# 2_IIP_RBF.net
KiCad netlist of a schematic drawn in Altium Designer
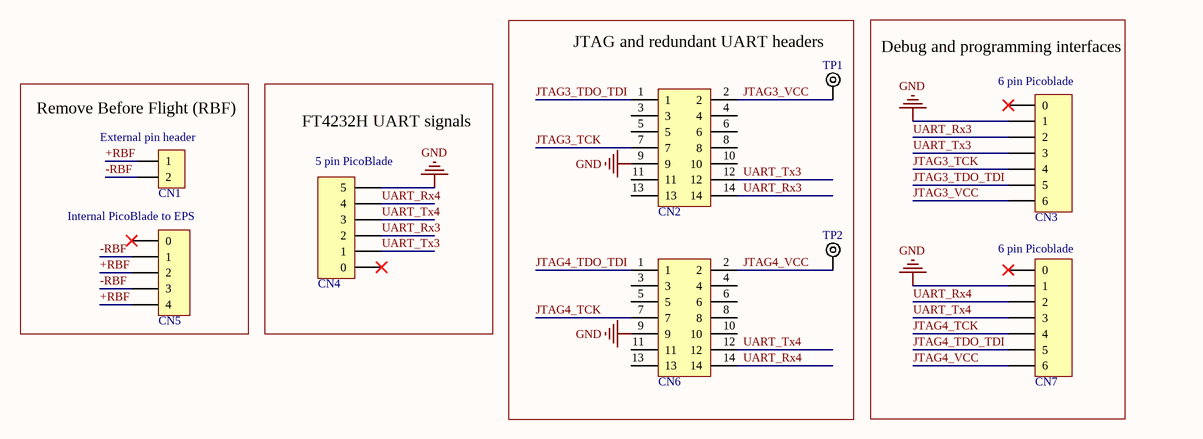
[diagram p0: 2_IIP_RBF.SchDoc]

(export (version "E")
  (design (tool "Eeschema 10.0.6"))
  (components
    (comp (ref "CN1")
      (value "2 POS Pin Header")
      (footprint "CONN HEADER VERT 2POS 2.54mm")
      (description "M20 HDR, PIN, SIL, VERT, 2W")
      (fields (field (name "MANUFACTURER") "Harwin") (field (name "VOLTAGE") "50V"))
      (libsource (lib "IB_floripasat2") (part "M20-9990245"))
    )
    (comp (ref "CN2")
      (value "7 POS dual line Pin Header 2.54mm")
      (footprint "CONN HEADER VERT 14POS 2.54MM")
      (description "Headers & Wire Housings 07+07 DIL VERTICAL PIN HEADER GOLD HT")
      (fields (field (name "MANUFACTURER") "Harwin") (field (name "MANUFACTURER PART NUMBER") "M20-9980745"))
      (libsource (lib "IB_floripasat2") (part "M20-9980745"))
    )
    (comp (ref "CN3")
      (value "6 pin Picoblade")
      (footprint "PICO BLADE 0533980671")
      (description "1.25mm Pitch PicoBlade™ Header, Surface Mount, Vertical, 6 Circuits")
      (fields (field (name "MANUFACTURER") "Molex") (field (name "MANUFACTURER PART NUMBER") "53398-0671"))
      (libsource (lib "IB_floripasat2") (part "53398-0671"))
    )
    (comp (ref "CN4")
      (value "5 pin PicoBlade")
      (footprint "PICO BLADE 0533980571")
      (description "Wire-To-Board Connector, Vertical, PicoBlade 53398 Series, Surface Mount, Header, 5, 1.25 mm")
      (fields (field (name "MANUFACTURER") "Molex") (field (name "MANUFACTURER PART NUMBER") "53398-0571"))
      (libsource (lib "IB_floripasat2") (part "53398-0571"))
    )
    (comp (ref "CN5")
      (value "4 pin Picoblade")
      (footprint "PICO BLADE 0533980471")
      (description "Connector Header Surface Mount 4 position 0.049\" (1.25mm)")
      (fields (field (name "MANUFACTURER") "Molex") (field (name "MANUFACTURER PART NUMBER") "53398-0471"))
      (libsource (lib "IB_floripasat2") (part "0533980471"))
    )
    (comp (ref "CN6")
      (value "7 POS dual line Pin Header 2.54mm")
      (footprint "CONN HEADER VERT 14POS 2.54MM")
      (description "Headers & Wire Housings 07+07 DIL VERTICAL PIN HEADER GOLD HT")
      (fields (field (name "MANUFACTURER") "Harwin") (field (name "MANUFACTURER PART NUMBER") "M20-9980745"))
      (libsource (lib "IB_floripasat2") (part "M20-9980745"))
    )
    (comp (ref "CN7")
      (value "6 pin Picoblade")
      (footprint "PICO BLADE 0533980671")
      (description "1.25mm Pitch PicoBlade™ Header, Surface Mount, Vertical, 6 Circuits")
      (fields (field (name "MANUFACTURER") "Molex") (field (name "MANUFACTURER PART NUMBER") "53398-0671"))
      (libsource (lib "IB_floripasat2") (part "53398-0671"))
    )
    (comp (ref "TP1")
      (value "DNP")
      (footprint "TEST POINT PTH")
      (description "TEST POINT PAD")
      (libsource (lib "IB_floripasat2") (part "Test Point PTH"))
    )
    (comp (ref "TP2")
      (value "DNP")
      (footprint "TEST POINT PTH")
      (description "TEST POINT PAD")
      (libsource (lib "IB_floripasat2") (part "Test Point PTH"))
    )
  )
  (nets
    (net (code "1") (name "/+RBF") (class "Default")
      (node (ref "CN1") (pin "1") (pinfunction "1_1") (pintype "passive"))
      (node (ref "CN5") (pin "2") (pinfunction "2_2") (pintype "passive"))
      (node (ref "CN5") (pin "4") (pinfunction "4_4") (pintype "passive"))
    )
    (net (code "2") (name "/-RBF") (class "Default")
      (node (ref "CN1") (pin "2") (pinfunction "2_2") (pintype "passive"))
      (node (ref "CN5") (pin "1") (pinfunction "1_1") (pintype "passive"))
      (node (ref "CN5") (pin "3") (pinfunction "3_3") (pintype "passive"))
    )
    (net (code "3") (name "/JTAG3_TCK") (class "Default")
      (node (ref "CN2") (pin "7") (pinfunction "7_7") (pintype "passive"))
      (node (ref "CN3") (pin "4") (pinfunction "4_4") (pintype "passive"))
    )
    (net (code "4") (name "/JTAG3_TDO_TDI") (class "Default")
      (node (ref "CN2") (pin "1") (pinfunction "1_1") (pintype "passive"))
      (node (ref "CN3") (pin "5") (pinfunction "5_5") (pintype "passive"))
    )
    (net (code "5") (name "/JTAG3_VCC") (class "Default")
      (node (ref "CN2") (pin "2") (pinfunction "2_2") (pintype "passive"))
      (node (ref "CN3") (pin "6") (pinfunction "6_6") (pintype "passive"))
      (node (ref "TP1") (pin "1") (pinfunction "1_1") (pintype "passive"))
    )
    (net (code "6") (name "/JTAG4_TCK") (class "Default")
      (node (ref "CN6") (pin "7") (pinfunction "7_7") (pintype "passive"))
      (node (ref "CN7") (pin "4") (pinfunction "4_4") (pintype "passive"))
    )
    (net (code "7") (name "/JTAG4_TDO_TDI") (class "Default")
      (node (ref "CN6") (pin "1") (pinfunction "1_1") (pintype "passive"))
      (node (ref "CN7") (pin "5") (pinfunction "5_5") (pintype "passive"))
    )
    (net (code "8") (name "/JTAG4_VCC") (class "Default")
      (node (ref "CN6") (pin "2") (pinfunction "2_2") (pintype "passive"))
      (node (ref "CN7") (pin "6") (pinfunction "6_6") (pintype "passive"))
      (node (ref "TP2") (pin "1") (pinfunction "1_1") (pintype "passive"))
    )
    (net (code "9") (name "/UART_Rx3") (class "Default")
      (node (ref "CN2") (pin "14") (pinfunction "14_14") (pintype "passive"))
      (node (ref "CN3") (pin "2") (pinfunction "2_2") (pintype "passive"))
      (node (ref "CN4") (pin "2") (pinfunction "2_2") (pintype "passive"))
    )
    (net (code "10") (name "/UART_Rx4") (class "Default")
      (node (ref "CN4") (pin "4") (pinfunction "4_4") (pintype "passive"))
      (node (ref "CN6") (pin "14") (pinfunction "14_14") (pintype "passive"))
      (node (ref "CN7") (pin "2") (pinfunction "2_2") (pintype "passive"))
    )
    (net (code "11") (name "/UART_Tx3") (class "Default")
      (node (ref "CN2") (pin "12") (pinfunction "12_12") (pintype "passive"))
      (node (ref "CN3") (pin "3") (pinfunction "3_3") (pintype "passive"))
      (node (ref "CN4") (pin "1") (pinfunction "1_1") (pintype "passive"))
    )
    (net (code "12") (name "/UART_Tx4") (class "Default")
      (node (ref "CN4") (pin "3") (pinfunction "3_3") (pintype "passive"))
      (node (ref "CN6") (pin "12") (pinfunction "12_12") (pintype "passive"))
      (node (ref "CN7") (pin "3") (pinfunction "3_3") (pintype "passive"))
    )
    (net (code "13") (name "GND") (class "Default")
      (node (ref "CN2") (pin "9") (pinfunction "9_9") (pintype "passive"))
      (node (ref "CN3") (pin "1") (pinfunction "1_1") (pintype "passive"))
      (node (ref "CN4") (pin "5") (pinfunction "5_5") (pintype "passive"))
      (node (ref "CN6") (pin "9") (pinfunction "9_9") (pintype "passive"))
      (node (ref "CN7") (pin "1") (pinfunction "1_1") (pintype "passive"))
    )
    (net (code "14") (name "unconnected-(CN2-Pad3)") (class "Default")
      (node (ref "CN2") (pin "3") (pinfunction "3_3") (pintype "passive"))
    )
    (net (code "15") (name "unconnected-(CN2-Pad4)") (class "Default")
      (node (ref "CN2") (pin "4") (pinfunction "4_4") (pintype "passive"))
    )
    (net (code "16") (name "unconnected-(CN2-Pad5)") (class "Default")
      (node (ref "CN2") (pin "5") (pinfunction "5_5") (pintype "passive"))
    )
    (net (code "17") (name "unconnected-(CN2-Pad6)") (class "Default")
      (node (ref "CN2") (pin "6") (pinfunction "6_6") (pintype "passive"))
    )
    (net (code "18") (name "unconnected-(CN2-Pad8)") (class "Default")
      (node (ref "CN2") (pin "8") (pinfunction "8_8") (pintype "passive"))
    )
    (net (code "19") (name "unconnected-(CN2-Pad10)") (class "Default")
      (node (ref "CN2") (pin "10") (pinfunction "10_10") (pintype "passive"))
    )
    (net (code "20") (name "unconnected-(CN2-Pad11)") (class "Default")
      (node (ref "CN2") (pin "11") (pinfunction "11_11") (pintype "passive"))
    )
    (net (code "21") (name "unconnected-(CN2-Pad13)") (class "Default")
      (node (ref "CN2") (pin "13") (pinfunction "13_13") (pintype "passive"))
    )
    (net (code "22") (name "unconnected-(CN3-Pad0)") (class "Default")
      (node (ref "CN3") (pin "0") (pinfunction "0_0") (pintype "passive+no_connect"))
    )
    (net (code "23") (name "unconnected-(CN4-Pad0)") (class "Default")
      (node (ref "CN4") (pin "0") (pinfunction "0_0") (pintype "passive+no_connect"))
    )
    (net (code "24") (name "unconnected-(CN5-Pad0)") (class "Default")
      (node (ref "CN5") (pin "0") (pinfunction "0_0") (pintype "passive+no_connect"))
    )
    (net (code "25") (name "unconnected-(CN6-Pad3)") (class "Default")
      (node (ref "CN6") (pin "3") (pinfunction "3_3") (pintype "passive"))
    )
    (net (code "26") (name "unconnected-(CN6-Pad4)") (class "Default")
      (node (ref "CN6") (pin "4") (pinfunction "4_4") (pintype "passive"))
    )
    (net (code "27") (name "unconnected-(CN6-Pad5)") (class "Default")
      (node (ref "CN6") (pin "5") (pinfunction "5_5") (pintype "passive"))
    )
    (net (code "28") (name "unconnected-(CN6-Pad6)") (class "Default")
      (node (ref "CN6") (pin "6") (pinfunction "6_6") (pintype "passive"))
    )
    (net (code "29") (name "unconnected-(CN6-Pad8)") (class "Default")
      (node (ref "CN6") (pin "8") (pinfunction "8_8") (pintype "passive"))
    )
    (net (code "30") (name "unconnected-(CN6-Pad10)") (class "Default")
      (node (ref "CN6") (pin "10") (pinfunction "10_10") (pintype "passive"))
    )
    (net (code "31") (name "unconnected-(CN6-Pad11)") (class "Default")
      (node (ref "CN6") (pin "11") (pinfunction "11_11") (pintype "passive"))
    )
    (net (code "32") (name "unconnected-(CN6-Pad13)") (class "Default")
      (node (ref "CN6") (pin "13") (pinfunction "13_13") (pintype "passive"))
    )
    (net (code "33") (name "unconnected-(CN7-Pad0)") (class "Default")
      (node (ref "CN7") (pin "0") (pinfunction "0_0") (pintype "passive+no_connect"))
    )
  )
)
